# opl2msx.net
KiCad netlist of a schematic drawn in EAGLE
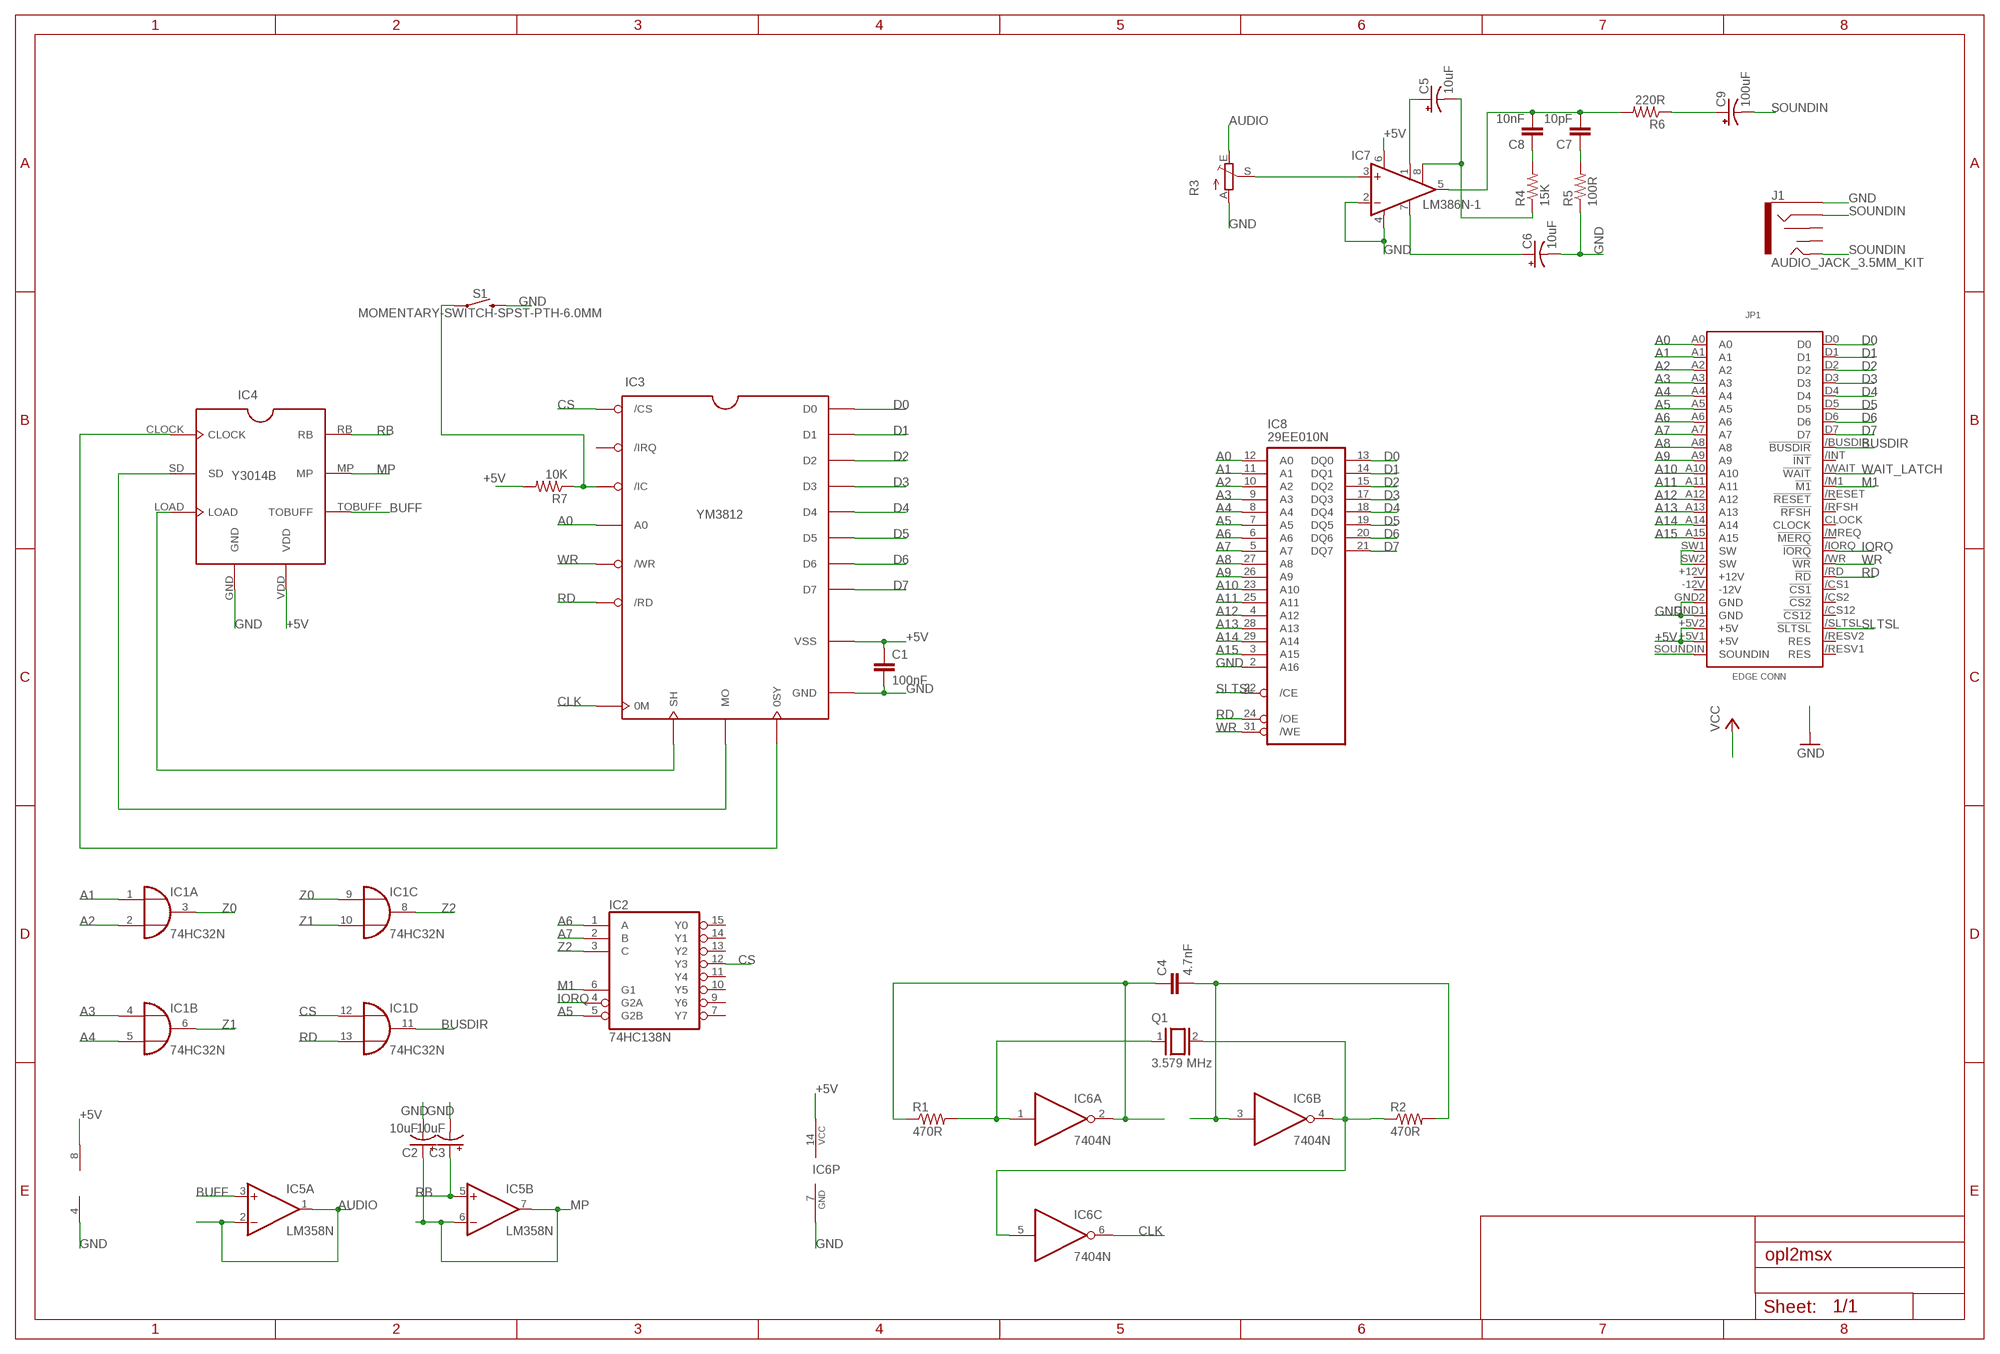
[diagram p0: schematic, sheet 1]

(export (version "E")
  (design (tool "Eeschema 10.0.6"))
  (components
    (comp (ref "C1")
      (value "100nF")
      (footprint "eagle-import:C050-024X044")
      (libsource (lib "eagle-import") (part "C-EU050-024X044"))
    )
    (comp (ref "C2")
      (value "10uF")
      (footprint "eagle-import:E2,5-6")
      (libsource (lib "eagle-import") (part "CPOL-USE2.5-6"))
    )
    (comp (ref "C3")
      (value "10uF")
      (footprint "eagle-import:E2,5-6")
      (libsource (lib "eagle-import") (part "CPOL-USE2.5-6"))
    )
    (comp (ref "C4")
      (value "4.7nF")
      (footprint "eagle-import:C050-024X044")
      (libsource (lib "eagle-import") (part "C-EU050-024X044"))
    )
    (comp (ref "C5")
      (value "10uF")
      (footprint "eagle-import:E2,5-6")
      (libsource (lib "eagle-import") (part "CPOL-USE2.5-6"))
    )
    (comp (ref "C6")
      (value "10uF")
      (footprint "eagle-import:E2,5-6")
      (libsource (lib "eagle-import") (part "CPOL-USE2.5-6"))
    )
    (comp (ref "C7")
      (value "10pF")
      (footprint "eagle-import:C050-024X044")
      (libsource (lib "eagle-import") (part "C-EU050-024X044"))
    )
    (comp (ref "C8")
      (value "10nF")
      (footprint "eagle-import:C050-024X044")
      (libsource (lib "eagle-import") (part "C-EU050-024X044"))
    )
    (comp (ref "C9")
      (value "100uF")
      (footprint "eagle-import:E2,5-6")
      (libsource (lib "eagle-import") (part "CPOL-USE2.5-6"))
    )
    (comp (ref "IC1")
      (value "74HC32N")
      (footprint "eagle-import:DIL14")
      (libsource (lib "eagle-import") (part "7432NHC"))
    )
    (comp (ref "IC2")
      (value "74HC138N")
      (footprint "eagle-import:DIL16")
      (libsource (lib "eagle-import") (part "74138NHC"))
    )
    (comp (ref "IC3")
      (value "YM3812")
      (footprint "eagle-import:YM3812")
      (libsource (lib "eagle-import") (part "YM3812-DIP24"))
    )
    (comp (ref "IC4")
      (value "Y3014B")
      (footprint "eagle-import:YM3014B")
      (libsource (lib "eagle-import") (part "YM3014B-DIP8"))
    )
    (comp (ref "IC5")
      (value "LM358N")
      (footprint "eagle-import:DIL08")
      (libsource (lib "eagle-import") (part "LM358N"))
    )
    (comp (ref "IC6")
      (value "7404N")
      (footprint "eagle-import:DIL14")
      (libsource (lib "eagle-import") (part "7404N"))
    )
    (comp (ref "IC7")
      (value "LM386N-1")
      (footprint "eagle-import:DIL08")
      (libsource (lib "eagle-import") (part "LM386?-N1"))
    )
    (comp (ref "IC8")
      (value "29EE010N")
      (footprint "eagle-import:DIL32-6")
      (libsource (lib "eagle-import") (part "29XE010N"))
    )
    (comp (ref "J1")
      (value "AUDIO_JACK_3.5MM_KIT")
      (footprint "eagle-import:AUDIO-JACK-KIT")
      (libsource (lib "eagle-import") (part "AUDIO_JACK_3.5MM_KIT"))
    )
    (comp (ref "JP1")
      (value "MSXCART")
      (footprint "eagle-import:PATOLA-MSX-SEEED")
      (libsource (lib "eagle-import") (part "MSXCART"))
    )
    (comp (ref "Q1")
      (value "3.579 MHz")
      (footprint "eagle-import:QS")
      (libsource (lib "eagle-import") (part "XTAL/S"))
    )
    (comp (ref "R1")
      (value "470R")
      (footprint "eagle-import:0207_10")
      (libsource (lib "eagle-import") (part "R-US_0207/10"))
    )
    (comp (ref "R2")
      (value "470R")
      (footprint "eagle-import:0207_10")
      (libsource (lib "eagle-import") (part "R-US_0207/10"))
    )
    (comp (ref "R3")
      (value "TRIM_EU-CA6V")
      (footprint "eagle-import:CA6V")
      (libsource (lib "eagle-import") (part "TRIM_EU-CA6V"))
    )
    (comp (ref "R4")
      (value "15K")
      (footprint "eagle-import:0207_10")
      (libsource (lib "eagle-import") (part "R-US_0207/10"))
    )
    (comp (ref "R5")
      (value "100R")
      (footprint "eagle-import:0207_10")
      (libsource (lib "eagle-import") (part "R-US_0207/10"))
    )
    (comp (ref "R6")
      (value "220R")
      (footprint "eagle-import:0207_10")
      (libsource (lib "eagle-import") (part "R-US_0207/10"))
    )
    (comp (ref "R7")
      (value "10K")
      (footprint "eagle-import:0207_10")
      (libsource (lib "eagle-import") (part "R-US_0207/10"))
    )
    (comp (ref "S1")
      (value "MOMENTARY-SWITCH-SPST-PTH-6.0MM")
      (footprint "eagle-import:TACTILE_SWITCH_PTH_6.0MM")
      (libsource (lib "eagle-import") (part "MOMENTARY-SWITCH-SPST-PTH-6.0MM"))
    )
  )
  (nets
    (net (code "1") (name "/+5V") (class "Default")
      (node (ref "C1") (pin "1") (pinfunction "1_1") (pintype "passive"))
      (node (ref "IC3") (pin "VSS") (pinfunction "VSS_VSS") (pintype "power_in"))
      (node (ref "IC4") (pin "VDD") (pinfunction "VDD_VDD") (pintype "power_in"))
      (node (ref "IC5") (pin "8") (pinfunction "V+_8") (pintype "power_in"))
      (node (ref "IC6") (pin "14") (pinfunction "VCC_14") (pintype "power_in"))
      (node (ref "IC7") (pin "6") (pinfunction "VS_6") (pintype "power_in"))
      (node (ref "JP1") (pin "+5V1") (pinfunction "+5V_+5V1") (pintype "power_in"))
      (node (ref "JP1") (pin "+5V2") (pinfunction "+5V_+5V2") (pintype "power_in"))
      (node (ref "R7") (pin "2") (pinfunction "2_2") (pintype "passive"))
    )
    (net (code "2") (name "/+12V") (class "Default")
      (node (ref "JP1") (pin "+12V") (pinfunction "+12V_+12V") (pintype "power_in"))
    )
    (net (code "3") (name "/-12V") (class "Default")
      (node (ref "JP1") (pin "-12V") (pinfunction "-12V_-12V") (pintype "power_in"))
    )
    (net (code "4") (name "/A0") (class "Default")
      (node (ref "IC3") (pin "A0") (pinfunction "A0_A0") (pintype "bidirectional"))
      (node (ref "IC8") (pin "12") (pinfunction "A0_12") (pintype "input"))
      (node (ref "JP1") (pin "A0") (pinfunction "A0_A0") (pintype "output"))
    )
    (net (code "5") (name "/A1") (class "Default")
      (node (ref "IC1") (pin "1") (pinfunction "I0_1") (pintype "input"))
      (node (ref "IC8") (pin "11") (pinfunction "A1_11") (pintype "input"))
      (node (ref "JP1") (pin "A1") (pinfunction "A1_A1") (pintype "output"))
    )
    (net (code "6") (name "/A2") (class "Default")
      (node (ref "IC1") (pin "2") (pinfunction "I1_2") (pintype "input"))
      (node (ref "IC8") (pin "10") (pinfunction "A2_10") (pintype "input"))
      (node (ref "JP1") (pin "A2") (pinfunction "A2_A2") (pintype "output"))
    )
    (net (code "7") (name "/A3") (class "Default")
      (node (ref "IC1") (pin "4") (pinfunction "I0_4") (pintype "input"))
      (node (ref "IC8") (pin "9") (pinfunction "A3_9") (pintype "input"))
      (node (ref "JP1") (pin "A3") (pinfunction "A3_A3") (pintype "output"))
    )
    (net (code "8") (name "/A4") (class "Default")
      (node (ref "IC1") (pin "5") (pinfunction "I1_5") (pintype "input"))
      (node (ref "IC8") (pin "8") (pinfunction "A4_8") (pintype "input"))
      (node (ref "JP1") (pin "A4") (pinfunction "A4_A4") (pintype "output"))
    )
    (net (code "9") (name "/A5") (class "Default")
      (node (ref "IC2") (pin "5") (pinfunction "G2B_5") (pintype "input"))
      (node (ref "IC8") (pin "7") (pinfunction "A5_7") (pintype "input"))
      (node (ref "JP1") (pin "A5") (pinfunction "A5_A5") (pintype "output"))
    )
    (net (code "10") (name "/A6") (class "Default")
      (node (ref "IC2") (pin "1") (pinfunction "A_1") (pintype "input"))
      (node (ref "IC8") (pin "6") (pinfunction "A6_6") (pintype "input"))
      (node (ref "JP1") (pin "A6") (pinfunction "A6_A6") (pintype "output"))
    )
    (net (code "11") (name "/A7") (class "Default")
      (node (ref "IC2") (pin "2") (pinfunction "B_2") (pintype "input"))
      (node (ref "IC8") (pin "5") (pinfunction "A7_5") (pintype "input"))
      (node (ref "JP1") (pin "A7") (pinfunction "A7_A7") (pintype "output"))
    )
    (net (code "12") (name "/A8") (class "Default")
      (node (ref "IC8") (pin "27") (pinfunction "A8_27") (pintype "input"))
      (node (ref "JP1") (pin "A8") (pinfunction "A8_A8") (pintype "output"))
    )
    (net (code "13") (name "/A9") (class "Default")
      (node (ref "IC8") (pin "26") (pinfunction "A9_26") (pintype "input"))
      (node (ref "JP1") (pin "A9") (pinfunction "A9_A9") (pintype "output"))
    )
    (net (code "14") (name "/A10") (class "Default")
      (node (ref "IC8") (pin "23") (pinfunction "A10_23") (pintype "input"))
      (node (ref "JP1") (pin "A10") (pinfunction "A10_A10") (pintype "output"))
    )
    (net (code "15") (name "/A11") (class "Default")
      (node (ref "IC8") (pin "25") (pinfunction "A11_25") (pintype "input"))
      (node (ref "JP1") (pin "A11") (pinfunction "A11_A11") (pintype "output"))
    )
    (net (code "16") (name "/A12") (class "Default")
      (node (ref "IC8") (pin "4") (pinfunction "A12_4") (pintype "input"))
      (node (ref "JP1") (pin "A12") (pinfunction "A12_A12") (pintype "output"))
    )
    (net (code "17") (name "/A13") (class "Default")
      (node (ref "IC8") (pin "28") (pinfunction "A13_28") (pintype "input"))
      (node (ref "JP1") (pin "A13") (pinfunction "A13_A13") (pintype "output"))
    )
    (net (code "18") (name "/A14") (class "Default")
      (node (ref "IC8") (pin "29") (pinfunction "A14_29") (pintype "input"))
      (node (ref "JP1") (pin "A14") (pinfunction "A14_A14") (pintype "output"))
    )
    (net (code "19") (name "/A15") (class "Default")
      (node (ref "IC8") (pin "3") (pinfunction "A15_3") (pintype "input"))
      (node (ref "JP1") (pin "A15") (pinfunction "A15_A15") (pintype "output"))
    )
    (net (code "20") (name "/AUDIO") (class "Default")
      (node (ref "IC5") (pin "1") (pinfunction "OUT_1") (pintype "output"))
      (node (ref "IC5") (pin "2") (pinfunction "-IN_2") (pintype "input"))
      (node (ref "R3") (pin "E") (pinfunction "E_E") (pintype "passive"))
    )
    (net (code "21") (name "/BUFF") (class "Default")
      (node (ref "IC4") (pin "TOBUFF") (pinfunction "TOBUFF_TOBUFF") (pintype "bidirectional"))
      (node (ref "IC5") (pin "3") (pinfunction "+IN_3") (pintype "input"))
    )
    (net (code "22") (name "/BUSDIR") (class "Default")
      (node (ref "IC1") (pin "11") (pinfunction "O_11") (pintype "output"))
      (node (ref "JP1") (pin "/BUSDIR") (pinfunction "~{BUSDIR}_/BUSDIR") (pintype "input"))
    )
    (net (code "23") (name "/CLK") (class "Default")
      (node (ref "IC3") (pin "0M") (pinfunction "0M_0M") (pintype "bidirectional"))
      (node (ref "IC6") (pin "6") (pinfunction "O_6") (pintype "output"))
    )
    (net (code "24") (name "/CS") (class "Default")
      (node (ref "IC1") (pin "12") (pinfunction "I0_12") (pintype "input"))
      (node (ref "IC2") (pin "12") (pinfunction "Y3_12") (pintype "output"))
      (node (ref "IC3") (pin "/CS") (pinfunction "/CS_/CS") (pintype "bidirectional"))
    )
    (net (code "25") (name "/D0") (class "Default")
      (node (ref "IC3") (pin "D0") (pinfunction "D0_D0") (pintype "power_in"))
      (node (ref "IC8") (pin "13") (pinfunction "DQ0_13") (pintype "bidirectional"))
      (node (ref "JP1") (pin "D0") (pinfunction "D0_D0") (pintype "bidirectional"))
    )
    (net (code "26") (name "/D1") (class "Default")
      (node (ref "IC3") (pin "D1") (pinfunction "D1_D1") (pintype "power_in"))
      (node (ref "IC8") (pin "14") (pinfunction "DQ1_14") (pintype "bidirectional"))
      (node (ref "JP1") (pin "D1") (pinfunction "D1_D1") (pintype "bidirectional"))
    )
    (net (code "27") (name "/D2") (class "Default")
      (node (ref "IC3") (pin "D2") (pinfunction "D2_D2") (pintype "power_in"))
      (node (ref "IC8") (pin "15") (pinfunction "DQ2_15") (pintype "bidirectional"))
      (node (ref "JP1") (pin "D2") (pinfunction "D2_D2") (pintype "bidirectional"))
    )
    (net (code "28") (name "/D3") (class "Default")
      (node (ref "IC3") (pin "D3") (pinfunction "D3_D3") (pintype "power_in"))
      (node (ref "IC8") (pin "17") (pinfunction "DQ3_17") (pintype "bidirectional"))
      (node (ref "JP1") (pin "D3") (pinfunction "D3_D3") (pintype "bidirectional"))
    )
    (net (code "29") (name "/D4") (class "Default")
      (node (ref "IC3") (pin "D4") (pinfunction "D4_D4") (pintype "power_in"))
      (node (ref "IC8") (pin "18") (pinfunction "DQ4_18") (pintype "bidirectional"))
      (node (ref "JP1") (pin "D4") (pinfunction "D4_D4") (pintype "bidirectional"))
    )
    (net (code "30") (name "/D5") (class "Default")
      (node (ref "IC3") (pin "D5") (pinfunction "D5_D5") (pintype "power_in"))
      (node (ref "IC8") (pin "19") (pinfunction "DQ5_19") (pintype "bidirectional"))
      (node (ref "JP1") (pin "D5") (pinfunction "D5_D5") (pintype "bidirectional"))
    )
    (net (code "31") (name "/D6") (class "Default")
      (node (ref "IC3") (pin "D6") (pinfunction "D6_D6") (pintype "power_in"))
      (node (ref "IC8") (pin "20") (pinfunction "DQ6_20") (pintype "bidirectional"))
      (node (ref "JP1") (pin "D6") (pinfunction "D6_D6") (pintype "bidirectional"))
    )
    (net (code "32") (name "/D7") (class "Default")
      (node (ref "IC3") (pin "D7") (pinfunction "D7_D7") (pintype "power_in"))
      (node (ref "IC8") (pin "21") (pinfunction "DQ7_21") (pintype "bidirectional"))
      (node (ref "JP1") (pin "D7") (pinfunction "D7_D7") (pintype "bidirectional"))
    )
    (net (code "33") (name "/IORQ") (class "Default")
      (node (ref "IC2") (pin "4") (pinfunction "G2A_4") (pintype "input"))
      (node (ref "JP1") (pin "/IORQ") (pinfunction "~{IORQ}_/IORQ") (pintype "output"))
    )
    (net (code "34") (name "/M1") (class "Default")
      (node (ref "IC2") (pin "6") (pinfunction "G1_6") (pintype "input"))
      (node (ref "JP1") (pin "/M1") (pinfunction "~{M1}_/M1") (pintype "output"))
    )
    (net (code "35") (name "/MP") (class "Default")
      (node (ref "C2") (pin "+") (pinfunction "+_+") (pintype "passive"))
      (node (ref "IC4") (pin "MP") (pinfunction "MP_MP") (pintype "bidirectional"))
      (node (ref "IC5") (pin "6") (pinfunction "-IN_6") (pintype "input"))
      (node (ref "IC5") (pin "7") (pinfunction "OUT_7") (pintype "output"))
    )
    (net (code "36") (name "/RB") (class "Default")
      (node (ref "C3") (pin "+") (pinfunction "+_+") (pintype "passive"))
      (node (ref "IC4") (pin "RB") (pinfunction "RB_RB") (pintype "bidirectional"))
      (node (ref "IC5") (pin "5") (pinfunction "+IN_5") (pintype "input"))
    )
    (net (code "37") (name "/RD") (class "Default")
      (node (ref "IC1") (pin "13") (pinfunction "I1_13") (pintype "input"))
      (node (ref "IC3") (pin "/RD") (pinfunction "/RD_/RD") (pintype "bidirectional"))
      (node (ref "IC8") (pin "24") (pinfunction "/OE_24") (pintype "input"))
      (node (ref "JP1") (pin "/RD") (pinfunction "~{RD}_/RD") (pintype "output"))
    )
    (net (code "38") (name "/SLTSL") (class "Default")
      (node (ref "IC8") (pin "22") (pinfunction "/CE_22") (pintype "input"))
      (node (ref "JP1") (pin "/SLTSL") (pinfunction "~{SLTSL}_/SLTSL") (pintype "output"))
    )
    (net (code "39") (name "/SOUNDIN") (class "Default")
      (node (ref "C9") (pin "-") (pinfunction "-_-") (pintype "passive"))
      (node (ref "J1") (pin "RING") (pinfunction "RING_RING") (pintype "bidirectional"))
      (node (ref "J1") (pin "TIP") (pinfunction "TIP_TIP") (pintype "bidirectional"))
      (node (ref "JP1") (pin "SOUNDIN") (pinfunction "SOUNDIN_SOUNDIN") (pintype "passive"))
    )
    (net (code "40") (name "/WAIT_LATCH") (class "Default")
      (node (ref "JP1") (pin "/WAIT") (pinfunction "~{WAIT}_/WAIT") (pintype "open_collector"))
    )
    (net (code "41") (name "/WR") (class "Default")
      (node (ref "IC3") (pin "/WR") (pinfunction "/WR_/WR") (pintype "bidirectional"))
      (node (ref "IC8") (pin "31") (pinfunction "/WE_31") (pintype "input"))
      (node (ref "JP1") (pin "/WR") (pinfunction "~{WR}_/WR") (pintype "output"))
    )
    (net (code "42") (name "/Z0") (class "Default")
      (node (ref "IC1") (pin "3") (pinfunction "O_3") (pintype "output"))
      (node (ref "IC1") (pin "9") (pinfunction "I0_9") (pintype "input"))
    )
    (net (code "43") (name "/Z1") (class "Default")
      (node (ref "IC1") (pin "10") (pinfunction "I1_10") (pintype "input"))
      (node (ref "IC1") (pin "6") (pinfunction "O_6") (pintype "output"))
    )
    (net (code "44") (name "/Z2") (class "Default")
      (node (ref "IC1") (pin "8") (pinfunction "O_8") (pintype "output"))
      (node (ref "IC2") (pin "3") (pinfunction "C_3") (pintype "input"))
    )
    (net (code "45") (name "GND") (class "Default")
      (node (ref "C1") (pin "2") (pinfunction "2_2") (pintype "passive"))
      (node (ref "C2") (pin "-") (pinfunction "-_-") (pintype "passive"))
      (node (ref "C3") (pin "-") (pinfunction "-_-") (pintype "passive"))
      (node (ref "C6") (pin "-") (pinfunction "-_-") (pintype "passive"))
      (node (ref "IC3") (pin "GND") (pinfunction "GND_GND") (pintype "power_in"))
      (node (ref "IC4") (pin "GND") (pinfunction "GND_GND") (pintype "power_in"))
      (node (ref "IC5") (pin "4") (pinfunction "V-_4") (pintype "power_in"))
      (node (ref "IC6") (pin "7") (pinfunction "GND_7") (pintype "power_in"))
      (node (ref "IC7") (pin "2") (pinfunction "-IN_2") (pintype "input"))
      (node (ref "IC7") (pin "4") (pinfunction "GND_4") (pintype "power_in"))
      (node (ref "IC8") (pin "2") (pinfunction "A16_2") (pintype "input"))
      (node (ref "J1") (pin "SLEEVE") (pinfunction "SLEEVE_SLEEVE") (pintype "bidirectional"))
      (node (ref "JP1") (pin "GND1") (pinfunction "GND_GND1") (pintype "power_in"))
      (node (ref "JP1") (pin "GND2") (pinfunction "GND_GND2") (pintype "power_in"))
      (node (ref "R3") (pin "A") (pinfunction "A_A") (pintype "passive"))
      (node (ref "R5") (pin "1") (pinfunction "1_1") (pintype "passive"))
      (node (ref "S1") (pin "3") (pinfunction "2_3") (pintype "passive"))
    )
    (net (code "46") (name "Net-(C5-Pad+)") (class "Default")
      (node (ref "C5") (pin "+") (pinfunction "+_+") (pintype "passive"))
      (node (ref "IC7") (pin "1") (pinfunction "GAIN_1") (pintype "passive"))
    )
    (net (code "47") (name "Net-(C5-Pad-)") (class "Default")
      (node (ref "C5") (pin "-") (pinfunction "-_-") (pintype "passive"))
      (node (ref "IC7") (pin "8") (pinfunction "GAIN_8") (pintype "passive"))
      (node (ref "R4") (pin "1") (pinfunction "1_1") (pintype "passive"))
    )
    (net (code "48") (name "Net-(C7-Pad1)") (class "Default")
      (node (ref "C7") (pin "1") (pinfunction "1_1") (pintype "passive"))
      (node (ref "R5") (pin "2") (pinfunction "2_2") (pintype "passive"))
    )
    (net (code "49") (name "Net-(C8-Pad1)") (class "Default")
      (node (ref "C8") (pin "1") (pinfunction "1_1") (pintype "passive"))
      (node (ref "R4") (pin "2") (pinfunction "2_2") (pintype "passive"))
    )
    (net (code "50") (name "Net-(C9-Pad+)") (class "Default")
      (node (ref "C9") (pin "+") (pinfunction "+_+") (pintype "passive"))
      (node (ref "R6") (pin "1") (pinfunction "1_1") (pintype "passive"))
    )
    (net (code "51") (name "Net-(IC3-Pad0SY)") (class "Default")
      (node (ref "IC3") (pin "0SY") (pinfunction "0SY_0SY") (pintype "bidirectional"))
      (node (ref "IC4") (pin "CLOCK") (pinfunction "CLOCK_CLOCK") (pintype "bidirectional"))
    )
    (net (code "52") (name "Net-(IC3-PadMO)") (class "Default")
      (node (ref "IC3") (pin "MO") (pinfunction "MO_MO") (pintype "bidirectional"))
      (node (ref "IC4") (pin "SD") (pinfunction "SD_SD") (pintype "bidirectional"))
    )
    (net (code "53") (name "Net-(IC3-PadSH)") (class "Default")
      (node (ref "IC3") (pin "SH") (pinfunction "SH_SH") (pintype "bidirectional"))
      (node (ref "IC4") (pin "LOAD") (pinfunction "LOAD_LOAD") (pintype "bidirectional"))
    )
    (net (code "54") (name "Net-(IC3-Pad{slash}IC)") (class "Default")
      (node (ref "IC3") (pin "/IC") (pinfunction "/IC_/IC") (pintype "bidirectional"))
      (node (ref "R7") (pin "1") (pinfunction "1_1") (pintype "passive"))
      (node (ref "S1") (pin "1") (pinfunction "1_1") (pintype "passive"))
    )
    (net (code "55") (name "Net-(IC6A-I)") (class "Default")
      (node (ref "IC6") (pin "1") (pinfunction "I_1") (pintype "input"))
      (node (ref "Q1") (pin "1") (pinfunction "1_1") (pintype "passive"))
      (node (ref "R1") (pin "2") (pinfunction "2_2") (pintype "passive"))
    )
    (net (code "56") (name "Net-(IC6A-O)") (class "Default")
      (node (ref "C4") (pin "1") (pinfunction "1_1") (pintype "passive"))
      (node (ref "IC6") (pin "2") (pinfunction "O_2") (pintype "output"))
      (node (ref "R1") (pin "1") (pinfunction "1_1") (pintype "passive"))
    )
    (net (code "57") (name "Net-(IC6B-I)") (class "Default")
      (node (ref "C4") (pin "2") (pinfunction "2_2") (pintype "passive"))
      (node (ref "IC6") (pin "3") (pinfunction "I_3") (pintype "input"))
      (node (ref "R2") (pin "2") (pinfunction "2_2") (pintype "passive"))
    )
    (net (code "58") (name "Net-(IC6B-O)") (class "Default")
      (node (ref "IC6") (pin "4") (pinfunction "O_4") (pintype "output"))
      (node (ref "IC6") (pin "5") (pinfunction "I_5") (pintype "input"))
      (node (ref "Q1") (pin "2") (pinfunction "2_2") (pintype "passive"))
      (node (ref "R2") (pin "1") (pinfunction "1_1") (pintype "passive"))
    )
    (net (code "59") (name "Net-(IC7-+IN)") (class "Default")
      (node (ref "IC7") (pin "3") (pinfunction "+IN_3") (pintype "input"))
      (node (ref "R3") (pin "S") (pinfunction "S_S") (pintype "passive"))
    )
    (net (code "60") (name "Net-(IC7-BYPASS)") (class "Default")
      (node (ref "C6") (pin "+") (pinfunction "+_+") (pintype "passive"))
      (node (ref "IC7") (pin "7") (pinfunction "BYPASS_7") (pintype "passive"))
    )
    (net (code "61") (name "Net-(IC7-OUT)") (class "Default")
      (node (ref "C7") (pin "2") (pinfunction "2_2") (pintype "passive"))
      (node (ref "C8") (pin "2") (pinfunction "2_2") (pintype "passive"))
      (node (ref "IC7") (pin "5") (pinfunction "OUT_5") (pintype "output"))
      (node (ref "R6") (pin "2") (pinfunction "2_2") (pintype "passive"))
    )
    (net (code "62") (name "Net-(JP1-SW-PadSW1)") (class "Default")
      (node (ref "JP1") (pin "SW1") (pinfunction "SW_SW1") (pintype "passive"))
      (node (ref "JP1") (pin "SW2") (pinfunction "SW_SW2") (pintype "passive"))
    )
    (net (code "64") (name "unconnected-(IC2A-Y0-Pad15)") (class "Default")
      (node (ref "IC2") (pin "15") (pinfunction "Y0_15") (pintype "output"))
    )
    (net (code "65") (name "unconnected-(IC2A-Y1-Pad14)") (class "Default")
      (node (ref "IC2") (pin "14") (pinfunction "Y1_14") (pintype "output"))
    )
    (net (code "66") (name "unconnected-(IC2A-Y2-Pad13)") (class "Default")
      (node (ref "IC2") (pin "13") (pinfunction "Y2_13") (pintype "output"))
    )
    (net (code "67") (name "unconnected-(IC2A-Y4-Pad11)") (class "Default")
      (node (ref "IC2") (pin "11") (pinfunction "Y4_11") (pintype "output"))
    )
    (net (code "68") (name "unconnected-(IC2A-Y5-Pad10)") (class "Default")
      (node (ref "IC2") (pin "10") (pinfunction "Y5_10") (pintype "output"))
    )
    (net (code "69") (name "unconnected-(IC2A-Y6-Pad9)") (class "Default")
      (node (ref "IC2") (pin "9") (pinfunction "Y6_9") (pintype "output"))
    )
    (net (code "70") (name "unconnected-(IC2A-Y7-Pad7)") (class "Default")
      (node (ref "IC2") (pin "7") (pinfunction "Y7_7") (pintype "output"))
    )
    (net (code "71") (name "unconnected-(IC3-Pad{slash}IRQ)") (class "Default")
      (node (ref "IC3") (pin "/IRQ") (pinfunction "/IRQ_/IRQ") (pintype "bidirectional"))
    )
    (net (code "72") (name "unconnected-(J1-PadRSH)") (class "Default")
      (node (ref "J1") (pin "RSH") (pinfunction "RSH_RSH") (pintype "bidirectional"))
    )
    (net (code "73") (name "unconnected-(J1-PadTSH)") (class "Default")
      (node (ref "J1") (pin "TSH") (pinfunction "TSH_TSH") (pintype "bidirectional"))
    )
    (net (code "74") (name "unconnected-(JP1-PadCLOCK)") (class "Default")
      (node (ref "JP1") (pin "CLOCK") (pinfunction "CLOCK_CLOCK") (pintype "output"))
    )
    (net (code "75") (name "unconnected-(JP1-RES-Pad{slash}RESV1)") (class "Default")
      (node (ref "JP1") (pin "/RESV1") (pinfunction "RES_/RESV1") (pintype "no_connect"))
    )
    (net (code "76") (name "unconnected-(JP1-RES-Pad{slash}RESV2)") (class "Default")
      (node (ref "JP1") (pin "/RESV2") (pinfunction "RES_/RESV2") (pintype "no_connect"))
    )
    (net (code "77") (name "unconnected-(JP1-~{CS1}-Pad{slash}CS1)") (class "Default")
      (node (ref "JP1") (pin "/CS1") (pinfunction "~{CS1}_/CS1") (pintype "output"))
    )
    (net (code "78") (name "unconnected-(JP1-~{CS2}-Pad{slash}CS2)") (class "Default")
      (node (ref "JP1") (pin "/CS2") (pinfunction "~{CS2}_/CS2") (pintype "output"))
    )
    (net (code "79") (name "unconnected-(JP1-~{CS12}-Pad{slash}CS12)") (class "Default")
      (node (ref "JP1") (pin "/CS12") (pinfunction "~{CS12}_/CS12") (pintype "output"))
    )
    (net (code "80") (name "unconnected-(JP1-~{INT}-Pad{slash}INT)") (class "Default")
      (node (ref "JP1") (pin "/INT") (pinfunction "~{INT}_/INT") (pintype "open_collector"))
    )
    (net (code "81") (name "unconnected-(JP1-~{MERQ}-Pad{slash}MREQ)") (class "Default")
      (node (ref "JP1") (pin "/MREQ") (pinfunction "~{MERQ}_/MREQ") (pintype "output"))
    )
    (net (code "82") (name "unconnected-(JP1-~{RESET}-Pad{slash}RESET)") (class "Default")
      (node (ref "JP1") (pin "/RESET") (pinfunction "~{RESET}_/RESET") (pintype "output"))
    )
    (net (code "83") (name "unconnected-(JP1-~{RFSH}-Pad{slash}RFSH)") (class "Default")
      (node (ref "JP1") (pin "/RFSH") (pinfunction "~{RFSH}_/RFSH") (pintype "output"))
    )
  )
)
